# 2.net
KiCad netlist of a schematic drawn in Altium Designer
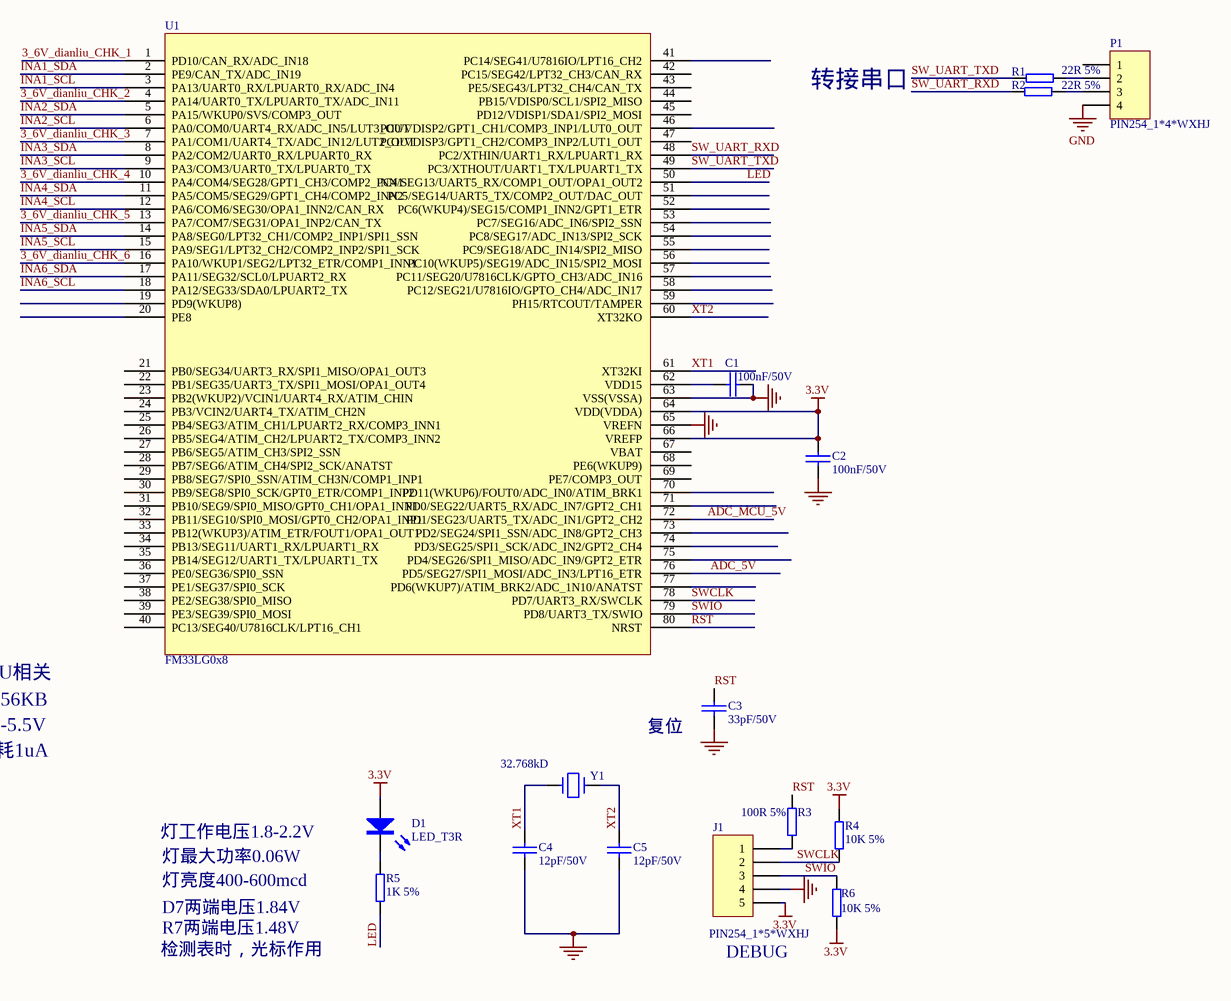
[diagram p0: 功耗测试工装原理图2.SchDoc]

(export (version "E")
  (design (tool "Eeschema 10.0.6"))
  (components
    (comp (ref "C1")
      (value "100nF/50V")
      (footprint "CAP0603")
      (description "104pF,50 V,±10%,0603,国巨,CC0603KRX7R9BB104")
      (fields (field (name "PART NUMBER") "101020103-0021"))
      (libsource (lib "Database_Libs2") (part "CC03K7R9_100N"))
    )
    (comp (ref "C2")
      (value "100nF/50V")
      (footprint "CAP0603")
      (description "104pF,50 V,±10%,0603,国巨,CC0603KRX7R9BB104")
      (fields (field (name "PART NUMBER") "101020103-0021"))
      (libsource (lib "Database_Libs2") (part "CC03K7R9_100N"))
    )
    (comp (ref "C3")
      (value "33pF/50V")
      (footprint "CAP0603")
      (description "33pF,50 V,±10%,0603,国巨,CC0603KRNPO9BN33")
      (fields (field (name "PART NUMBER") "101020103-0027"))
      (libsource (lib "Database_Libs2") (part "CC03KPO9_33P"))
    )
    (comp (ref "C4")
      (value "12pF/50V")
      (footprint "CAP0603")
      (description "12P,50 V,±5%,0603,国巨,CC0603JRNPO9BN12")
      (fields (field (name "PART NUMBER") "101020103-0005"))
      (libsource (lib "Database_Libs2") (part "CC03JPO9_12P"))
    )
    (comp (ref "C5")
      (value "12pF/50V")
      (footprint "CAP0603")
      (description "12P,50 V,±5%,0603,国巨,CC0603JRNPO9BN12")
      (fields (field (name "PART NUMBER") "101020103-0005"))
      (libsource (lib "Database_Libs2") (part "CC03JPO9_12P"))
    )
    (comp (ref "D1")
      (value "LED_T3R")
      (footprint "LED2_300")
      (description "圆形插件,3mm 圆形,插件,红光,湖北匡通电子有限公司,3BB4HC")
      (fields (field (name "PART NUMBER") "101040102-0001"))
      (libsource (lib "Database_Libs2") (part "01-LED_T3R"))
    )
    (comp (ref "J1")
      (value "PIN254_1*5*WXHJ")
      (footprint "PIN254_1*5*1100S")
      (description "1*5 ，Φ1.0 ，2.54mm，直脚,无需焊接器件")
      (fields (field (name "PART NUMBER") "AD_WXHJ_PinHeader_02"))
      (libsource (lib "Database_Libs2") (part "PIN254_1*5*1100S"))
    )
    (comp (ref "P1")
      (value "PIN254_1*4*WXHJ")
      (footprint "PIN254_1*4*1100S")
      (description "1*4 ，Φ1.0 ，2.54mm，直脚,无需焊接器件")
      (fields (field (name "PART NUMBER") "AD_WXHJ_PinHeader_01"))
      (libsource (lib "Database_Libs2") (part "PIN254_1*4*1100S"))
    )
    (comp (ref "R1")
      (value "22R 5%")
      (footprint "RES0603")
      (description "国巨,±5%,0603,,155 ℃,-55 ℃,RC0603JR-0722RL,无铅,200 ppm/℃,1/10W,,22欧")
      (fields (field (name "PART NUMBER") "101010103-0009"))
      (libsource (lib "Database_Libs2") (part "RC03J_22R"))
    )
    (comp (ref "R2")
      (value "22R 5%")
      (footprint "RES0603")
      (description "国巨,±5%,0603,,155 ℃,-55 ℃,RC0603JR-0722RL,无铅,200 ppm/℃,1/10W,,22欧")
      (fields (field (name "PART NUMBER") "101010103-0009"))
      (libsource (lib "Database_Libs2") (part "RC03J_22R"))
    )
    (comp (ref "R3")
      (value "100R 5%")
      (footprint "RES0603")
      (description "100R,±5%,1/10W,0603,国巨,RC0603JR-07100RL")
      (fields (field (name "PART NUMBER") "101010103-0022"))
      (libsource (lib "Database_Libs2") (part "RC03J_100R"))
    )
    (comp (ref "R4")
      (value "10K 5%")
      (footprint "RES0603")
      (description "国巨,±5%,0603,,155 ℃,-55 ℃,RC0603JR-0710KL,无铅,200 ppm/℃,1/10W,,10K")
      (fields (field (name "PART NUMBER") "101010103-0003"))
      (libsource (lib "Database_Libs2") (part "RC03J_10K"))
    )
    (comp (ref "R5")
      (value "1K 5%")
      (footprint "RES0603")
      (description "1K,±5%,1/10W,0603,国巨,RC0603JR-071KL")
      (fields (field (name "PART NUMBER") "101010103-0008"))
      (libsource (lib "Database_Libs2") (part "RC03J_1K"))
    )
    (comp (ref "R6")
      (value "10K 5%")
      (footprint "RES0603")
      (description "国巨,±5%,0603,,155 ℃,-55 ℃,RC0603JR-0710KL,无铅,200 ppm/℃,1/10W,,10K")
      (fields (field (name "PART NUMBER") "101010103-0003"))
      (libsource (lib "Database_Libs2") (part "RC03J_10K"))
    )
    (comp (ref "U1") (value "FM33LG0x8") (footprint "LQFP80") (libsource (lib "FM_MCU") (part "FM33LG0x8")))
    (comp (ref "Y1")
      (value "32.768kD")
      (footprint "SMD-3215_2P")
      (fields (field (name "PART NUMBER") "1010601-0020"))
      (libsource (lib "Database_Libs2") (part "04_XTALSG12MD_32.768kD"))
    )
  )
  (nets
    (net (code "1") (name "/3_6V_dianliu_CHK_1") (class "Default")
      (node (ref "U1") (pin "1") (pinfunction "PD10/CAN_RX/ADC_IN18_1") (pintype "passive"))
    )
    (net (code "2") (name "/3_6V_dianliu_CHK_2") (class "Default")
      (node (ref "U1") (pin "4") (pinfunction "PA14/UART0_TX/LPUART0_TX/ADC_IN11_4") (pintype "passive"))
    )
    (net (code "3") (name "/3_6V_dianliu_CHK_3") (class "Default")
      (node (ref "U1") (pin "7") (pinfunction "PA1/COM1/UART4_TX/ADC_IN12/LUT2_OUT_7") (pintype "passive"))
    )
    (net (code "4") (name "/3_6V_dianliu_CHK_4") (class "Default")
      (node (ref "U1") (pin "10") (pinfunction "PA4/COM4/SEG28/GPT1_CH3/COMP2_INN1_10") (pintype "passive"))
    )
    (net (code "5") (name "/3_6V_dianliu_CHK_5") (class "Default")
      (node (ref "U1") (pin "13") (pinfunction "PA7/COM7/SEG31/OPA1_INP2/CAN_TX_13") (pintype "passive"))
    )
    (net (code "6") (name "/3_6V_dianliu_CHK_6") (class "Default")
      (node (ref "U1") (pin "16") (pinfunction "PA10/WKUP1/SEG2/LPT32_ETR/COMP1_INN1_16") (pintype "passive"))
    )
    (net (code "7") (name "/ADC_5V") (class "Default")
      (node (ref "U1") (pin "76") (pinfunction "PD5/SEG27/SPI1_MOSI/ADC_IN3/LPT16_ETR_76") (pintype "passive"))
    )
    (net (code "8") (name "/ADC_MCU_5V") (class "Default")
      (node (ref "U1") (pin "72") (pinfunction "PD1/SEG23/UART5_TX/ADC_IN1/GPT2_CH2_72") (pintype "passive"))
    )
    (net (code "9") (name "/INA1_SCL") (class "Default")
      (node (ref "U1") (pin "3") (pinfunction "PA13/UART0_RX/LPUART0_RX/ADC_IN4_3") (pintype "passive"))
    )
    (net (code "10") (name "/INA1_SDA") (class "Default")
      (node (ref "U1") (pin "2") (pinfunction "PE9/CAN_TX/ADC_IN19_2") (pintype "passive"))
    )
    (net (code "11") (name "/INA2_SCL") (class "Default")
      (node (ref "U1") (pin "6") (pinfunction "PA0/COM0/UART4_RX/ADC_IN5/LUT3_OUT_6") (pintype "passive"))
    )
    (net (code "12") (name "/INA2_SDA") (class "Default")
      (node (ref "U1") (pin "5") (pinfunction "PA15/WKUP0/SVS/COMP3_OUT_5") (pintype "passive"))
    )
    (net (code "13") (name "/INA3_SCL") (class "Default")
      (node (ref "U1") (pin "9") (pinfunction "PA3/COM3/UART0_TX/LPUART0_TX_9") (pintype "passive"))
    )
    (net (code "14") (name "/INA3_SDA") (class "Default")
      (node (ref "U1") (pin "8") (pinfunction "PA2/COM2/UART0_RX/LPUART0_RX_8") (pintype "passive"))
    )
    (net (code "15") (name "/INA4_SCL") (class "Default")
      (node (ref "U1") (pin "12") (pinfunction "PA6/COM6/SEG30/OPA1_INN2/CAN_RX_12") (pintype "passive"))
    )
    (net (code "16") (name "/INA4_SDA") (class "Default")
      (node (ref "U1") (pin "11") (pinfunction "PA5/COM5/SEG29/GPT1_CH4/COMP2_INN2_11") (pintype "passive"))
    )
    (net (code "17") (name "/INA5_SCL") (class "Default")
      (node (ref "U1") (pin "15") (pinfunction "PA9/SEG1/LPT32_CH2/COMP2_INP2/SPI1_SCK_15") (pintype "passive"))
    )
    (net (code "18") (name "/INA5_SDA") (class "Default")
      (node (ref "U1") (pin "14") (pinfunction "PA8/SEG0/LPT32_CH1/COMP2_INP1/SPI1_SSN_14") (pintype "passive"))
    )
    (net (code "19") (name "/INA6_SCL") (class "Default")
      (node (ref "U1") (pin "18") (pinfunction "PA12/SEG33/SDA0/LPUART2_TX_18") (pintype "passive"))
    )
    (net (code "20") (name "/INA6_SDA") (class "Default")
      (node (ref "U1") (pin "17") (pinfunction "PA11/SEG32/SCL0/LPUART2_RX_17") (pintype "passive"))
    )
    (net (code "21") (name "/LED") (class "Default")
      (node (ref "R5") (pin "1") (pinfunction "1_1") (pintype "passive"))
      (node (ref "U1") (pin "50") (pinfunction "PC4/SEG13/UART5_RX/COMP1_OUT/OPA1_OUT2_50") (pintype "passive"))
    )
    (net (code "22") (name "/RST") (class "Default")
      (node (ref "C3") (pin "1") (pinfunction "1_1") (pintype "passive"))
      (node (ref "R3") (pin "1") (pinfunction "1_1") (pintype "passive"))
      (node (ref "U1") (pin "80") (pinfunction "NRST_80") (pintype "passive"))
    )
    (net (code "23") (name "/SWCLK") (class "Default")
      (node (ref "J1") (pin "2") (pinfunction "2_2") (pintype "passive"))
      (node (ref "R4") (pin "2") (pinfunction "2_2") (pintype "passive"))
      (node (ref "U1") (pin "78") (pinfunction "PD7/UART3_RX/SWCLK_78") (pintype "passive"))
    )
    (net (code "24") (name "/SWIO") (class "Default")
      (node (ref "J1") (pin "3") (pinfunction "3_3") (pintype "passive"))
      (node (ref "R6") (pin "2") (pinfunction "2_2") (pintype "passive"))
      (node (ref "U1") (pin "79") (pinfunction "PD8/UART3_TX/SWIO_79") (pintype "passive"))
    )
    (net (code "25") (name "/SW_UART_RXD") (class "Default")
      (node (ref "R2") (pin "1") (pinfunction "1_1") (pintype "passive"))
      (node (ref "U1") (pin "48") (pinfunction "PC2/XTHIN/UART1_RX/LPUART1_RX_48") (pintype "passive"))
    )
    (net (code "26") (name "/SW_UART_TXD") (class "Default")
      (node (ref "R1") (pin "1") (pinfunction "1_1") (pintype "passive"))
      (node (ref "U1") (pin "49") (pinfunction "PC3/XTHOUT/UART1_TX/LPUART1_TX_49") (pintype "passive"))
    )
    (net (code "27") (name "/XT1") (class "Default")
      (node (ref "C4") (pin "1") (pinfunction "1_1") (pintype "passive"))
      (node (ref "U1") (pin "61") (pinfunction "XT32KI_61") (pintype "passive"))
      (node (ref "Y1") (pin "1") (pinfunction "1_1") (pintype "passive"))
    )
    (net (code "28") (name "/XT2") (class "Default")
      (node (ref "C5") (pin "2") (pinfunction "2_2") (pintype "passive"))
      (node (ref "U1") (pin "60") (pinfunction "XT32KO_60") (pintype "passive"))
      (node (ref "Y1") (pin "2") (pinfunction "2_2") (pintype "passive"))
    )
    (net (code "29") (name "3.3V") (class "Default")
      (node (ref "C2") (pin "2") (pinfunction "2_2") (pintype "passive"))
      (node (ref "D1") (pin "1") (pinfunction "1_1") (pintype "passive"))
      (node (ref "J1") (pin "5") (pinfunction "5_5") (pintype "passive"))
      (node (ref "R4") (pin "1") (pinfunction "1_1") (pintype "passive"))
      (node (ref "R6") (pin "1") (pinfunction "1_1") (pintype "passive"))
      (node (ref "U1") (pin "64") (pinfunction "VDD(VDDA)_64") (pintype "passive"))
      (node (ref "U1") (pin "66") (pinfunction "VREFP_66") (pintype "passive"))
    )
    (net (code "30") (name "GND") (class "Default")
      (node (ref "C1") (pin "2") (pinfunction "2_2") (pintype "passive"))
      (node (ref "C2") (pin "1") (pinfunction "1_1") (pintype "passive"))
      (node (ref "C3") (pin "2") (pinfunction "2_2") (pintype "passive"))
      (node (ref "C4") (pin "2") (pinfunction "2_2") (pintype "passive"))
      (node (ref "C5") (pin "1") (pinfunction "1_1") (pintype "passive"))
      (node (ref "J1") (pin "4") (pinfunction "4_4") (pintype "passive"))
      (node (ref "P1") (pin "4") (pinfunction "4_4") (pintype "passive"))
      (node (ref "U1") (pin "63") (pinfunction "VSS(VSSA)_63") (pintype "passive"))
      (node (ref "U1") (pin "65") (pinfunction "VREFN_65") (pintype "passive"))
    )
    (net (code "31") (name "Net-(D1-Pad2)") (class "Default")
      (node (ref "D1") (pin "2") (pinfunction "2_2") (pintype "passive"))
      (node (ref "R5") (pin "2") (pinfunction "2_2") (pintype "passive"))
    )
    (net (code "32") (name "Net-(J1-Pad1)") (class "Default")
      (node (ref "J1") (pin "1") (pinfunction "1_1") (pintype "passive"))
      (node (ref "R3") (pin "2") (pinfunction "2_2") (pintype "passive"))
    )
    (net (code "33") (name "Net-(P1-Pad2)") (class "Default")
      (node (ref "P1") (pin "2") (pinfunction "2_2") (pintype "passive"))
      (node (ref "R1") (pin "2") (pinfunction "2_2") (pintype "passive"))
    )
    (net (code "34") (name "Net-(P1-Pad3)") (class "Default")
      (node (ref "P1") (pin "3") (pinfunction "3_3") (pintype "passive"))
      (node (ref "R2") (pin "2") (pinfunction "2_2") (pintype "passive"))
    )
    (net (code "35") (name "Net-(U1-VDD15)") (class "Default")
      (node (ref "C1") (pin "1") (pinfunction "1_1") (pintype "passive"))
      (node (ref "U1") (pin "62") (pinfunction "VDD15_62") (pintype "passive"))
    )
    (net (code "36") (name "unconnected-(P1-Pad1)") (class "Default")
      (node (ref "P1") (pin "1") (pinfunction "1_1") (pintype "passive"))
    )
    (net (code "37") (name "unconnected-(U1-PB0{slash}SEG34{slash}UART3_RX{slash}SPI1_MISO{slash}OPA1_OUT3-Pad21)") (class "Default")
      (node (ref "U1") (pin "21") (pinfunction "PB0/SEG34/UART3_RX/SPI1_MISO/OPA1_OUT3_21") (pintype "passive"))
    )
    (net (code "38") (name "unconnected-(U1-PB1{slash}SEG35{slash}UART3_TX{slash}SPI1_MOSI{slash}OPA1_OUT4-Pad22)") (class "Default")
      (node (ref "U1") (pin "22") (pinfunction "PB1/SEG35/UART3_TX/SPI1_MOSI/OPA1_OUT4_22") (pintype "passive"))
    )
    (net (code "39") (name "unconnected-(U1-PB2(WKUP2){slash}VCIN1{slash}UART4_RX{slash}ATIM_CHIN-Pad23)") (class "Default")
      (node (ref "U1") (pin "23") (pinfunction "PB2(WKUP2)/VCIN1/UART4_RX/ATIM_CHIN_23") (pintype "passive"))
    )
    (net (code "40") (name "unconnected-(U1-PB3{slash}VCIN2{slash}UART4_TX{slash}ATIM_CH2N-Pad24)") (class "Default")
      (node (ref "U1") (pin "24") (pinfunction "PB3/VCIN2/UART4_TX/ATIM_CH2N_24") (pintype "passive"))
    )
    (net (code "41") (name "unconnected-(U1-PB4{slash}SEG3{slash}ATIM_CH1{slash}LPUART2_RX{slash}COMP3_INN1-Pad25)") (class "Default")
      (node (ref "U1") (pin "25") (pinfunction "PB4/SEG3/ATIM_CH1/LPUART2_RX/COMP3_INN1_25") (pintype "passive"))
    )
    (net (code "42") (name "unconnected-(U1-PB5{slash}SEG4{slash}ATIM_CH2{slash}LPUART2_TX{slash}COMP3_INN2-Pad26)") (class "Default")
      (node (ref "U1") (pin "26") (pinfunction "PB5/SEG4/ATIM_CH2/LPUART2_TX/COMP3_INN2_26") (pintype "passive"))
    )
    (net (code "43") (name "unconnected-(U1-PB6{slash}SEG5{slash}ATIM_CH3{slash}SPI2_SSN-Pad27)") (class "Default")
      (node (ref "U1") (pin "27") (pinfunction "PB6/SEG5/ATIM_CH3/SPI2_SSN_27") (pintype "passive"))
    )
    (net (code "44") (name "unconnected-(U1-PB7{slash}SEG6{slash}ATIM_CH4{slash}SPI2_SCK{slash}ANATST-Pad28)") (class "Default")
      (node (ref "U1") (pin "28") (pinfunction "PB7/SEG6/ATIM_CH4/SPI2_SCK/ANATST_28") (pintype "passive"))
    )
    (net (code "45") (name "unconnected-(U1-PB8{slash}SEG7{slash}SPI0_SSN{slash}ATIM_CH3N{slash}COMP1_INP1-Pad29)") (class "Default")
      (node (ref "U1") (pin "29") (pinfunction "PB8/SEG7/SPI0_SSN/ATIM_CH3N/COMP1_INP1_29") (pintype "passive"))
    )
    (net (code "46") (name "unconnected-(U1-PB9{slash}SEG8{slash}SPI0_SCK{slash}GPT0_ETR{slash}COMP1_INP2-Pad30)") (class "Default")
      (node (ref "U1") (pin "30") (pinfunction "PB9/SEG8/SPI0_SCK/GPT0_ETR/COMP1_INP2_30") (pintype "passive"))
    )
    (net (code "47") (name "unconnected-(U1-PB10{slash}SEG9{slash}SPI0_MISO{slash}GPT0_CH1{slash}OPA1_INN1-Pad31)") (class "Default")
      (node (ref "U1") (pin "31") (pinfunction "PB10/SEG9/SPI0_MISO/GPT0_CH1/OPA1_INN1_31") (pintype "passive"))
    )
    (net (code "48") (name "unconnected-(U1-PB11{slash}SEG10{slash}SPI0_MOSI{slash}GPT0_CH2{slash}OPA1_INP1-Pad32)") (class "Default")
      (node (ref "U1") (pin "32") (pinfunction "PB11/SEG10/SPI0_MOSI/GPT0_CH2/OPA1_INP1_32") (pintype "passive"))
    )
    (net (code "49") (name "unconnected-(U1-PB12(WKUP3){slash}ATIM_ETR{slash}FOUT1{slash}OPA1_OUT1-Pad33)") (class "Default")
      (node (ref "U1") (pin "33") (pinfunction "PB12(WKUP3)/ATIM_ETR/FOUT1/OPA1_OUT1_33") (pintype "passive"))
    )
    (net (code "50") (name "unconnected-(U1-PB13{slash}SEG11{slash}UART1_RX{slash}LPUART1_RX-Pad34)") (class "Default")
      (node (ref "U1") (pin "34") (pinfunction "PB13/SEG11/UART1_RX/LPUART1_RX_34") (pintype "passive"))
    )
    (net (code "51") (name "unconnected-(U1-PB14{slash}SEG12{slash}UART1_TX{slash}LPUART1_TX-Pad35)") (class "Default")
      (node (ref "U1") (pin "35") (pinfunction "PB14/SEG12/UART1_TX/LPUART1_TX_35") (pintype "passive"))
    )
    (net (code "52") (name "unconnected-(U1-PB15{slash}VDISP0{slash}SCL1{slash}SPI2_MISO-Pad44)") (class "Default")
      (node (ref "U1") (pin "44") (pinfunction "PB15/VDISP0/SCL1/SPI2_MISO_44") (pintype "passive"))
    )
    (net (code "53") (name "unconnected-(U1-PC0{slash}VDISP2{slash}GPT1_CH1{slash}COMP3_INP1{slash}LUT0_OUT-Pad46)") (class "Default")
      (node (ref "U1") (pin "46") (pinfunction "PC0/VDISP2/GPT1_CH1/COMP3_INP1/LUT0_OUT_46") (pintype "passive"))
    )
    (net (code "54") (name "unconnected-(U1-PC1{slash}VDISP3{slash}GPT1_CH2{slash}COMP3_INP2{slash}LUT1_OUT-Pad47)") (class "Default")
      (node (ref "U1") (pin "47") (pinfunction "PC1/VDISP3/GPT1_CH2/COMP3_INP2/LUT1_OUT_47") (pintype "passive"))
    )
    (net (code "55") (name "unconnected-(U1-PC5{slash}SEG14{slash}UART5_TX{slash}COMP2_OUT{slash}DAC_OUT-Pad51)") (class "Default")
      (node (ref "U1") (pin "51") (pinfunction "PC5/SEG14/UART5_TX/COMP2_OUT/DAC_OUT_51") (pintype "passive"))
    )
    (net (code "56") (name "unconnected-(U1-PC6(WKUP4){slash}SEG15{slash}COMP1_INN2{slash}GPT1_ETR-Pad52)") (class "Default")
      (node (ref "U1") (pin "52") (pinfunction "PC6(WKUP4)/SEG15/COMP1_INN2/GPT1_ETR_52") (pintype "passive"))
    )
    (net (code "57") (name "unconnected-(U1-PC7{slash}SEG16{slash}ADC_IN6{slash}SPI2_SSN-Pad53)") (class "Default")
      (node (ref "U1") (pin "53") (pinfunction "PC7/SEG16/ADC_IN6/SPI2_SSN_53") (pintype "passive"))
    )
    (net (code "58") (name "unconnected-(U1-PC8{slash}SEG17{slash}ADC_IN13{slash}SPI2_SCK-Pad54)") (class "Default")
      (node (ref "U1") (pin "54") (pinfunction "PC8/SEG17/ADC_IN13/SPI2_SCK_54") (pintype "passive"))
    )
    (net (code "59") (name "unconnected-(U1-PC9{slash}SEG18{slash}ADC_IN14{slash}SPI2_MISO-Pad55)") (class "Default")
      (node (ref "U1") (pin "55") (pinfunction "PC9/SEG18/ADC_IN14/SPI2_MISO_55") (pintype "passive"))
    )
    (net (code "60") (name "unconnected-(U1-PC10(WKUP5){slash}SEG19{slash}ADC_IN15{slash}SPI2_MOSI-Pad56)") (class "Default")
      (node (ref "U1") (pin "56") (pinfunction "PC10(WKUP5)/SEG19/ADC_IN15/SPI2_MOSI_56") (pintype "passive"))
    )
    (net (code "61") (name "unconnected-(U1-PC11{slash}SEG20{slash}U7816CLK{slash}GPTO_CH3{slash}ADC_IN16-Pad57)") (class "Default")
      (node (ref "U1") (pin "57") (pinfunction "PC11/SEG20/U7816CLK/GPTO_CH3/ADC_IN16_57") (pintype "passive"))
    )
    (net (code "62") (name "unconnected-(U1-PC12{slash}SEG21{slash}U7816IO{slash}GPTO_CH4{slash}ADC_IN17-Pad58)") (class "Default")
      (node (ref "U1") (pin "58") (pinfunction "PC12/SEG21/U7816IO/GPTO_CH4/ADC_IN17_58") (pintype "passive"))
    )
    (net (code "63") (name "unconnected-(U1-PC13{slash}SEG40{slash}U7816CLK{slash}LPT16_CH1-Pad40)") (class "Default")
      (node (ref "U1") (pin "40") (pinfunction "PC13/SEG40/U7816CLK/LPT16_CH1_40") (pintype "passive"))
    )
    (net (code "64") (name "unconnected-(U1-PC14{slash}SEG41{slash}U7816IO{slash}LPT16_CH2-Pad41)") (class "Default")
      (node (ref "U1") (pin "41") (pinfunction "PC14/SEG41/U7816IO/LPT16_CH2_41") (pintype "passive"))
    )
    (net (code "65") (name "unconnected-(U1-PC15{slash}SEG42{slash}LPT32_CH3{slash}CAN_RX-Pad42)") (class "Default")
      (node (ref "U1") (pin "42") (pinfunction "PC15/SEG42/LPT32_CH3/CAN_RX_42") (pintype "passive"))
    )
    (net (code "66") (name "unconnected-(U1-PD0{slash}SEG22{slash}UART5_RX{slash}ADC_IN7{slash}GPT2_CH1-Pad71)") (class "Default")
      (node (ref "U1") (pin "71") (pinfunction "PD0/SEG22/UART5_RX/ADC_IN7/GPT2_CH1_71") (pintype "passive"))
    )
    (net (code "67") (name "unconnected-(U1-PD2{slash}SEG24{slash}SPI1_SSN{slash}ADC_IN8{slash}GPT2_CH3-Pad73)") (class "Default")
      (node (ref "U1") (pin "73") (pinfunction "PD2/SEG24/SPI1_SSN/ADC_IN8/GPT2_CH3_73") (pintype "passive"))
    )
    (net (code "68") (name "unconnected-(U1-PD3{slash}SEG25{slash}SPI1_SCK{slash}ADC_IN2{slash}GPT2_CH4-Pad74)") (class "Default")
      (node (ref "U1") (pin "74") (pinfunction "PD3/SEG25/SPI1_SCK/ADC_IN2/GPT2_CH4_74") (pintype "passive"))
    )
    (net (code "69") (name "unconnected-(U1-PD4{slash}SEG26{slash}SPI1_MISO{slash}ADC_IN9{slash}GPT2_ETR-Pad75)") (class "Default")
      (node (ref "U1") (pin "75") (pinfunction "PD4/SEG26/SPI1_MISO/ADC_IN9/GPT2_ETR_75") (pintype "passive"))
    )
    (net (code "70") (name "unconnected-(U1-PD6(WKUP7){slash}ATIM_BRK2{slash}ADC_1N10{slash}ANATST-Pad77)") (class "Default")
      (node (ref "U1") (pin "77") (pinfunction "PD6(WKUP7)/ATIM_BRK2/ADC_1N10/ANATST_77") (pintype "passive"))
    )
    (net (code "71") (name "unconnected-(U1-PD9(WKUP8)-Pad19)") (class "Default")
      (node (ref "U1") (pin "19") (pinfunction "PD9(WKUP8)_19") (pintype "passive"))
    )
    (net (code "72") (name "unconnected-(U1-PD11(WKUP6){slash}FOUT0{slash}ADC_IN0{slash}ATIM_BRK1-Pad70)") (class "Default")
      (node (ref "U1") (pin "70") (pinfunction "PD11(WKUP6)/FOUT0/ADC_IN0/ATIM_BRK1_70") (pintype "passive"))
    )
    (net (code "73") (name "unconnected-(U1-PD12{slash}VDISP1{slash}SDA1{slash}SPI2_MOSI-Pad45)") (class "Default")
      (node (ref "U1") (pin "45") (pinfunction "PD12/VDISP1/SDA1/SPI2_MOSI_45") (pintype "passive"))
    )
    (net (code "74") (name "unconnected-(U1-PE0{slash}SEG36{slash}SPI0_SSN-Pad36)") (class "Default")
      (node (ref "U1") (pin "36") (pinfunction "PE0/SEG36/SPI0_SSN_36") (pintype "passive"))
    )
    (net (code "75") (name "unconnected-(U1-PE1{slash}SEG37{slash}SPI0_SCK-Pad37)") (class "Default")
      (node (ref "U1") (pin "37") (pinfunction "PE1/SEG37/SPI0_SCK_37") (pintype "passive"))
    )
    (net (code "76") (name "unconnected-(U1-PE2{slash}SEG38{slash}SPI0_MISO-Pad38)") (class "Default")
      (node (ref "U1") (pin "38") (pinfunction "PE2/SEG38/SPI0_MISO_38") (pintype "passive"))
    )
    (net (code "77") (name "unconnected-(U1-PE3{slash}SEG39{slash}SPI0_MOSI-Pad39)") (class "Default")
      (node (ref "U1") (pin "39") (pinfunction "PE3/SEG39/SPI0_MOSI_39") (pintype "passive"))
    )
    (net (code "78") (name "unconnected-(U1-PE5{slash}SEG43{slash}LPT32_CH4{slash}CAN_TX-Pad43)") (class "Default")
      (node (ref "U1") (pin "43") (pinfunction "PE5/SEG43/LPT32_CH4/CAN_TX_43") (pintype "passive"))
    )
    (net (code "79") (name "unconnected-(U1-PE6(WKUP9)-Pad68)") (class "Default")
      (node (ref "U1") (pin "68") (pinfunction "PE6(WKUP9)_68") (pintype "passive"))
    )
    (net (code "80") (name "unconnected-(U1-PE7{slash}COMP3_OUT-Pad69)") (class "Default")
      (node (ref "U1") (pin "69") (pinfunction "PE7/COMP3_OUT_69") (pintype "passive"))
    )
    (net (code "81") (name "unconnected-(U1-PE8-Pad20)") (class "Default")
      (node (ref "U1") (pin "20") (pinfunction "PE8_20") (pintype "passive"))
    )
    (net (code "82") (name "unconnected-(U1-PH15{slash}RTCOUT{slash}TAMPER-Pad59)") (class "Default")
      (node (ref "U1") (pin "59") (pinfunction "PH15/RTCOUT/TAMPER_59") (pintype "passive"))
    )
    (net (code "83") (name "unconnected-(U1-VBAT-Pad67)") (class "Default")
      (node (ref "U1") (pin "67") (pinfunction "VBAT_67") (pintype "passive"))
    )
  )
)
